# CAN_Sheet.net
KiCad netlist of a schematic drawn in Altium Designer
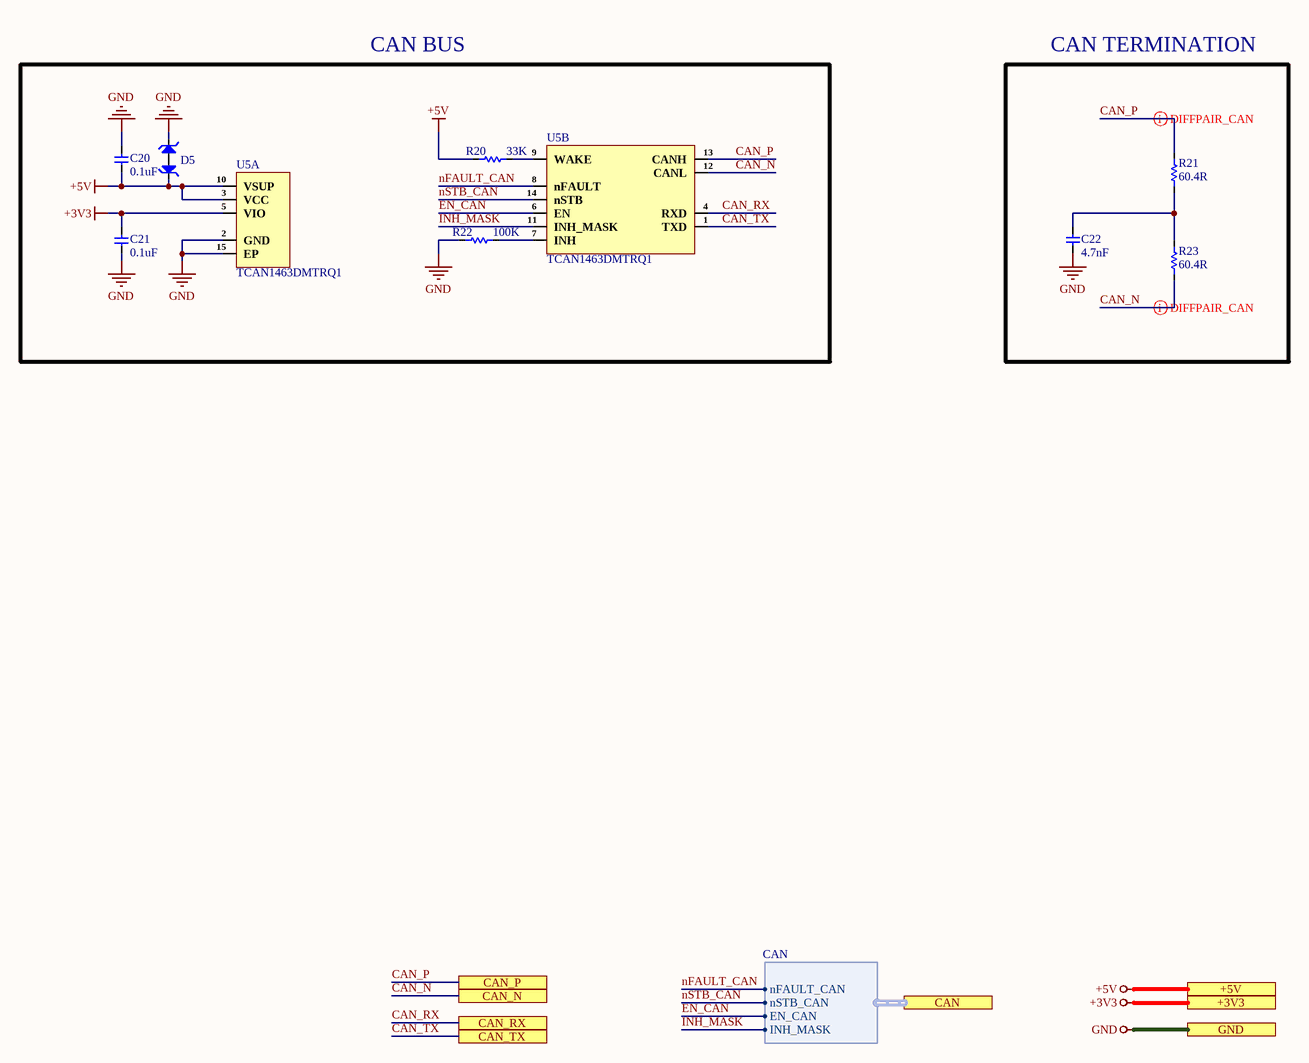
[diagram p0: CAN_Sheet.SchDoc]

(export (version "E")
  (design (tool "Eeschema 10.0.6"))
  (components
    (comp (ref "C20")
      (value "0.1uF")
      (footprint "Cap-0402")
      (description "CAP CER 0.1UF 16V X7R 0402")
      (fields
        (field (name "MANUFACTURER") "Yageo")
        (field (name "MANUFACTURER PART NUMBER") "CC0402JRX7R7BB104")
      )
      (libsource (lib "eSpark Libraries") (part "CC0402JRX7R7BB104"))
    )
    (comp (ref "C21")
      (value "0.1uF")
      (footprint "Cap-0402")
      (description "CAP CER 0.1UF 16V X7R 0402")
      (fields
        (field (name "MANUFACTURER") "Yageo")
        (field (name "MANUFACTURER PART NUMBER") "CC0402JRX7R7BB104")
      )
      (libsource (lib "eSpark Libraries") (part "CC0402JRX7R7BB104"))
    )
    (comp (ref "C22")
      (value "4.7nF")
      (footprint "Cap-0402")
      (description "CAP CER 4700PF 50V X7R 0402")
      (fields
        (field (name "MANUFACTURER") "Yageo")
        (field (name "MANUFACTURER PART NUMBER") "CC0402KRX7R9BB472")
      )
      (libsource (lib "eSpark Libraries") (part "CC0402KRX7R9BB472"))
    )
    (comp (ref "D5")
      (value "PESD5V0H1BSFYL")
      (footprint "DSN0603-2")
      (description "TVS DIODE 5VWM 6.3VC DSN0603-2")
      (fields (field (name "MANUFACTURER") "Nexperia") (field (name "LCSC PART NUMBER") "C477989"))
      (libsource (lib "eSpark Libraries") (part "PESD5V0H1BSFYL"))
    )
    (comp (ref "R20")
      (value "33K")
      (footprint "Res-0402")
      (description "RES 33K OHM 1% 1/16W 0402")
      (fields
        (field (name "MANUFACTURER") "YAGEO")
        (field (name "MANUFACTURER PART NUMBER") "RC0402FR-0733KL")
      )
      (libsource (lib "eSpark Libraries") (part "RC0402FR-0733KL"))
    )
    (comp (ref "R21")
      (value "60.4R")
      (footprint "Res-0603")
      (description "100mW Thick Film Resistors ±100ppm/℃ ±1% 60.4Ω 0603 Chip Resistor - Surface Mount ROHS")
      (fields
        (field (name "MANUFACTURER PART NUMBER") "RTT0360R4FTP")
        (field (name "LCSC PART NUMBER") "C103744")
      )
      (libsource (lib "eSpark Libraries") (part "RTT0360R4FTP"))
    )
    (comp (ref "R22")
      (value "100K")
      (footprint "Res-0402")
      (description "RES 100K OHM 1% 1/16W 0402")
      (fields
        (field (name "MANUFACTURER") "Yageo")
        (field (name "MANUFACTURER PART NUMBER") "RC0402FR-07100KL")
      )
      (libsource (lib "eSpark Libraries") (part "RC0402FR-07100KL"))
    )
    (comp (ref "R23")
      (value "60.4R")
      (footprint "Res-0603")
      (description "100mW Thick Film Resistors ±100ppm/℃ ±1% 60.4Ω 0603 Chip Resistor - Surface Mount ROHS")
      (fields
        (field (name "MANUFACTURER PART NUMBER") "RTT0360R4FTP")
        (field (name "LCSC PART NUMBER") "C103744")
      )
      (libsource (lib "eSpark Libraries") (part "RTT0360R4FTP"))
    )
    (comp (ref "U5")
      (value "TCAN1463DMTRQ1")
      (footprint "VSON-14(3x4.5)")
      (description "IC TRANSCEIVER HALF 1/1 14VSON")
      (fields (field (name "MANUFACTURER") "Texas Instruments") (field (name "LCSC PART NUMBER") "C5215823"))
      (libsource (lib "eSpark Libraries") (part "TCAN1463DMTRQ1"))
    )
  )
  (nets
    (net (code "2") (name "+3V3") (class "Default")
      (node (ref "C21") (pin "2") (pinfunction "2_2") (pintype "passive"))
      (node (ref "U5") (pin "5") (pinfunction "VIO_5") (pintype "passive"))
    )
    (net (code "3") (name "+5V") (class "Default")
      (node (ref "C20") (pin "1") (pinfunction "1_1") (pintype "passive"))
      (node (ref "D5") (pin "1") (pinfunction "1_1") (pintype "passive"))
      (node (ref "R20") (pin "1") (pinfunction "1_1") (pintype "passive"))
      (node (ref "U5") (pin "10") (pinfunction "VSUP_10") (pintype "passive"))
      (node (ref "U5") (pin "3") (pinfunction "VCC_3") (pintype "passive"))
    )
    (net (code "4") (name "/CAN_N") (class "Default")
      (node (ref "R23") (pin "2") (pinfunction "2_2") (pintype "passive"))
      (node (ref "U5") (pin "12") (pinfunction "CANL_12") (pintype "passive"))
    )
    (net (code "5") (name "/CAN_P") (class "Default")
      (node (ref "R21") (pin "1") (pinfunction "1_1") (pintype "passive"))
      (node (ref "U5") (pin "13") (pinfunction "CANH_13") (pintype "passive"))
    )
    (net (code "6") (name "/CAN_RX") (class "Default")
      (node (ref "U5") (pin "4") (pinfunction "RXD_4") (pintype "passive"))
    )
    (net (code "7") (name "/CAN_TX") (class "Default")
      (node (ref "U5") (pin "1") (pinfunction "TXD_1") (pintype "passive"))
    )
    (net (code "8") (name "/EN_CAN") (class "Default")
      (node (ref "U5") (pin "6") (pinfunction "EN_6") (pintype "passive"))
    )
    (net (code "9") (name "/INH_MASK") (class "Default")
      (node (ref "U5") (pin "11") (pinfunction "INH_MASK_11") (pintype "passive"))
    )
    (net (code "10") (name "/nFAULT_CAN") (class "Default")
      (node (ref "U5") (pin "8") (pinfunction "nFAULT_8") (pintype "passive"))
    )
    (net (code "11") (name "/nSTB_CAN") (class "Default")
      (node (ref "U5") (pin "14") (pinfunction "nSTB_14") (pintype "passive"))
    )
    (net (code "13") (name "GND") (class "Default")
      (node (ref "C20") (pin "2") (pinfunction "2_2") (pintype "passive"))
      (node (ref "C21") (pin "1") (pinfunction "1_1") (pintype "passive"))
      (node (ref "C22") (pin "2") (pinfunction "2_2") (pintype "passive"))
      (node (ref "D5") (pin "2") (pinfunction "2_2") (pintype "passive"))
      (node (ref "R22") (pin "1") (pinfunction "1_1") (pintype "passive"))
      (node (ref "U5") (pin "15") (pinfunction "EP_15") (pintype "passive"))
      (node (ref "U5") (pin "2") (pinfunction "GND_2") (pintype "passive"))
    )
    (net (code "14") (name "Net-(C22-Pad1)") (class "Default")
      (node (ref "C22") (pin "1") (pinfunction "1_1") (pintype "passive"))
      (node (ref "R21") (pin "2") (pinfunction "2_2") (pintype "passive"))
      (node (ref "R23") (pin "1") (pinfunction "1_1") (pintype "passive"))
    )
    (net (code "15") (name "Net-(U5B-INH)") (class "Default")
      (node (ref "R22") (pin "2") (pinfunction "2_2") (pintype "passive"))
      (node (ref "U5") (pin "7") (pinfunction "INH_7") (pintype "passive"))
    )
    (net (code "16") (name "Net-(U5B-WAKE)") (class "Default")
      (node (ref "R20") (pin "2") (pinfunction "2_2") (pintype "passive"))
      (node (ref "U5") (pin "9") (pinfunction "WAKE_9") (pintype "passive"))
    )
  )
)
